# LTC3108breakoutSSOC.net
KiCad netlist of a schematic drawn in EAGLE
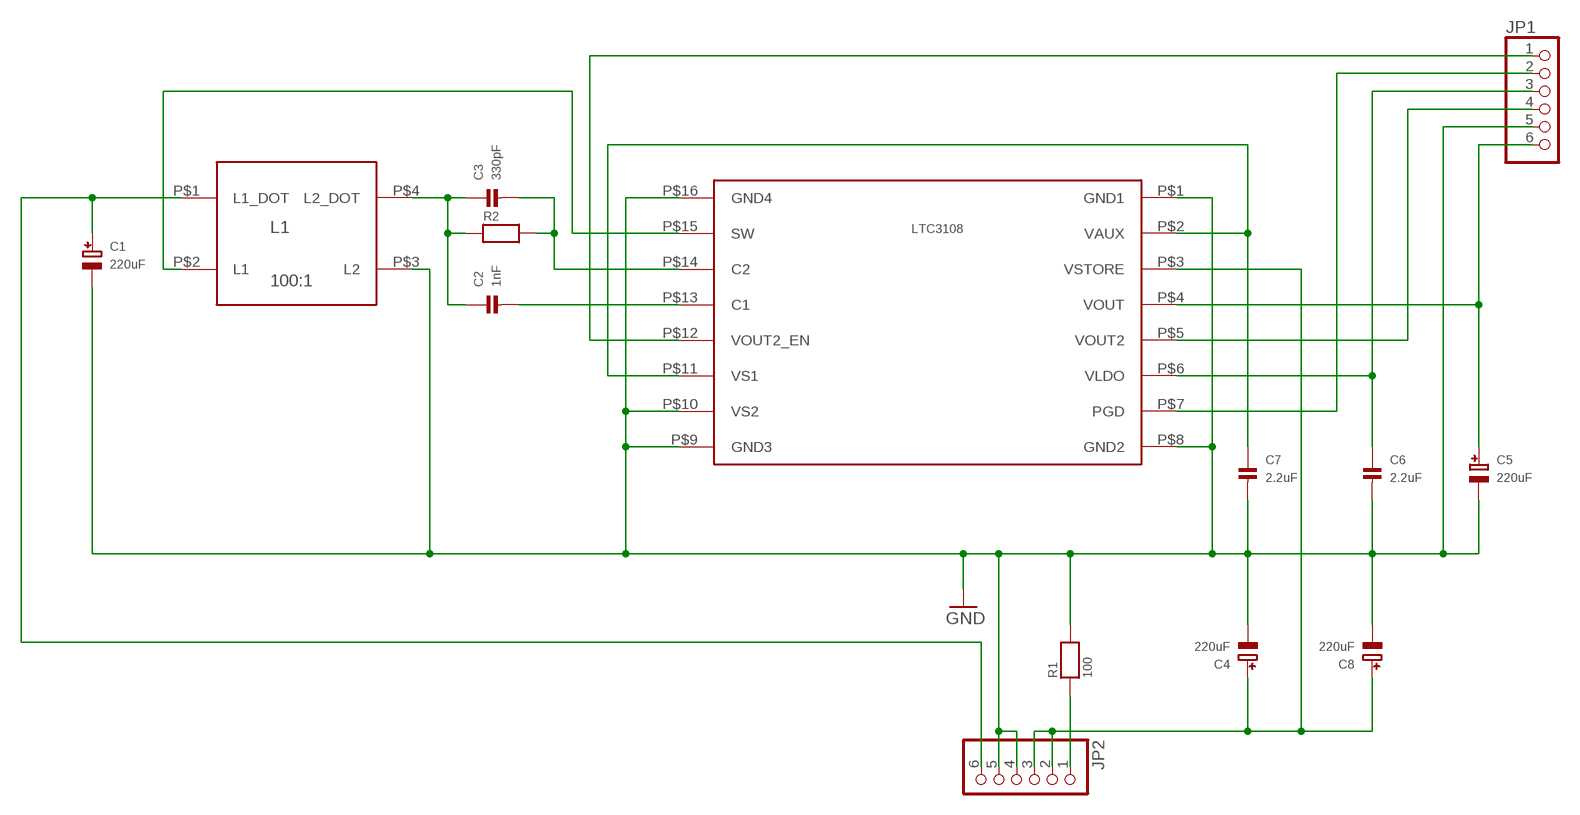
[diagram p0: schematic, sheet 1]

(export (version "E")
  (design (tool "Eeschema 10.0.6"))
  (components
    (comp (ref "C1")
      (value "220uF")
      (footprint "eagle-import:EIA7343-31_D-R")
      (libsource (lib "eagle-import") (part "CAP_TANTALUMD/7343_REFLOW"))
    )
    (comp (ref "C2")
      (value "1nF")
      (footprint "eagle-import:0603")
      (libsource (lib "eagle-import") (part "CAP_CERAMIC0603"))
    )
    (comp (ref "C3")
      (value "330pF")
      (footprint "eagle-import:0603")
      (libsource (lib "eagle-import") (part "CAP_CERAMIC0603"))
    )
    (comp (ref "C4")
      (value "220uF")
      (footprint "eagle-import:EIA7343-31_D-R")
      (libsource (lib "eagle-import") (part "CAP_TANTALUMD/7343_REFLOW"))
    )
    (comp (ref "C5")
      (value "220uF")
      (footprint "eagle-import:EIA7343-31_D-R")
      (libsource (lib "eagle-import") (part "CAP_TANTALUMD/7343_REFLOW"))
    )
    (comp (ref "C6")
      (value "2.2uF")
      (footprint "eagle-import:0603")
      (libsource (lib "eagle-import") (part "CAP_CERAMIC0603"))
    )
    (comp (ref "C7")
      (value "2.2uF")
      (footprint "eagle-import:0603")
      (libsource (lib "eagle-import") (part "CAP_CERAMIC0603"))
    )
    (comp (ref "C8")
      (value "220uF")
      (footprint "eagle-import:EIA7343-31_D-R")
      (libsource (lib "eagle-import") (part "CAP_TANTALUMD/7343_REFLOW"))
    )
    (comp (ref "JP1")
      (value "HEADER-1X6ROUND")
      (footprint "eagle-import:1X06_ROUND")
      (libsource (lib "eagle-import") (part "HEADER-1X6ROUND"))
    )
    (comp (ref "JP2")
      (value "HEADER-1X6ROUND")
      (footprint "eagle-import:1X06_ROUND")
      (libsource (lib "eagle-import") (part "HEADER-1X6ROUND"))
    )
    (comp (ref "L1")
      (value "100:1")
      (footprint "eagle-import:COILCRAFT_LPR6235")
      (libsource (lib "eagle-import") (part "COILCRAFT_LPR6235-752SML"))
    )
    (comp (ref "LTC3108")
      (value "LTC3108-SSOP")
      (footprint "eagle-import:SSOP-GN-16")
      (libsource (lib "eagle-import") (part "LTC3108-SSOP"))
    )
    (comp (ref "R1")
      (value "100")
      (footprint "eagle-import:0603")
      (libsource (lib "eagle-import") (part "RESISTOR0603"))
    )
    (comp (ref "R2")
      (value "RESISTOR0603")
      (footprint "eagle-import:0603")
      (libsource (lib "eagle-import") (part "RESISTOR0603"))
    )
  )
  (nets
    (net (code "1") (name "GND") (class "Default")
      (node (ref "C1") (pin "-") (pinfunction "-_-") (pintype "passive"))
      (node (ref "C4") (pin "-") (pinfunction "-_-") (pintype "passive"))
      (node (ref "C5") (pin "-") (pinfunction "-_-") (pintype "passive"))
      (node (ref "C6") (pin "2") (pinfunction "P$2_2") (pintype "passive"))
      (node (ref "C7") (pin "2") (pinfunction "P$2_2") (pintype "passive"))
      (node (ref "C8") (pin "-") (pinfunction "-_-") (pintype "passive"))
      (node (ref "JP1") (pin "5") (pinfunction "5_5") (pintype "passive"))
      (node (ref "JP2") (pin "4") (pinfunction "4_4") (pintype "passive"))
      (node (ref "JP2") (pin "5") (pinfunction "5_5") (pintype "passive"))
      (node (ref "L1") (pin "P$3") (pinfunction "L2_P$3") (pintype "bidirectional"))
      (node (ref "LTC3108") (pin "P$1") (pinfunction "GND1_P$1") (pintype "bidirectional"))
      (node (ref "LTC3108") (pin "P$10") (pinfunction "VS2_P$10") (pintype "bidirectional"))
      (node (ref "LTC3108") (pin "P$16") (pinfunction "GND4_P$16") (pintype "bidirectional"))
      (node (ref "LTC3108") (pin "P$8") (pinfunction "GND2_P$8") (pintype "bidirectional"))
      (node (ref "LTC3108") (pin "P$9") (pinfunction "GND3_P$9") (pintype "bidirectional"))
      (node (ref "R1") (pin "2") (pinfunction "2_2") (pintype "passive"))
    )
    (net (code "2") (name "Net-(C2-P$1)") (class "Default")
      (node (ref "C2") (pin "1") (pinfunction "P$1_1") (pintype "passive"))
      (node (ref "C3") (pin "1") (pinfunction "P$1_1") (pintype "passive"))
      (node (ref "L1") (pin "P$4") (pinfunction "L2_DOT_P$4") (pintype "bidirectional"))
      (node (ref "R2") (pin "1") (pinfunction "1_1") (pintype "passive"))
    )
    (net (code "3") (name "Net-(C2-P$2)") (class "Default")
      (node (ref "C2") (pin "2") (pinfunction "P$2_2") (pintype "passive"))
      (node (ref "LTC3108") (pin "P$13") (pinfunction "C1_P$13") (pintype "bidirectional"))
    )
    (net (code "4") (name "Net-(C3-P$2)") (class "Default")
      (node (ref "C3") (pin "2") (pinfunction "P$2_2") (pintype "passive"))
      (node (ref "LTC3108") (pin "P$14") (pinfunction "C2_P$14") (pintype "bidirectional"))
      (node (ref "R2") (pin "2") (pinfunction "2_2") (pintype "passive"))
    )
    (net (code "5") (name "Net-(C6-P$1)") (class "Default")
      (node (ref "C6") (pin "1") (pinfunction "P$1_1") (pintype "passive"))
      (node (ref "JP1") (pin "3") (pinfunction "3_3") (pintype "passive"))
      (node (ref "LTC3108") (pin "P$6") (pinfunction "VLDO_P$6") (pintype "bidirectional"))
    )
    (net (code "6") (name "Net-(C7-P$1)") (class "Default")
      (node (ref "C7") (pin "1") (pinfunction "P$1_1") (pintype "passive"))
      (node (ref "LTC3108") (pin "P$11") (pinfunction "VS1_P$11") (pintype "bidirectional"))
      (node (ref "LTC3108") (pin "P$2") (pinfunction "VAUX_P$2") (pintype "bidirectional"))
    )
    (net (code "7") (name "Net-(JP2-Pad1)") (class "Default")
      (node (ref "JP2") (pin "1") (pinfunction "1_1") (pintype "passive"))
      (node (ref "R1") (pin "1") (pinfunction "1_1") (pintype "passive"))
    )
    (net (code "8") (name "Net-(L1-L1)") (class "Default")
      (node (ref "L1") (pin "P$2") (pinfunction "L1_P$2") (pintype "bidirectional"))
      (node (ref "LTC3108") (pin "P$15") (pinfunction "SW_P$15") (pintype "bidirectional"))
    )
    (net (code "9") (name "Net-(L1-L1_DOT)") (class "Default")
      (node (ref "C1") (pin "+") (pinfunction "+_+") (pintype "passive"))
      (node (ref "JP2") (pin "6") (pinfunction "6_6") (pintype "passive"))
      (node (ref "L1") (pin "P$1") (pinfunction "L1_DOT_P$1") (pintype "bidirectional"))
    )
    (net (code "10") (name "Net-(LTC3108-PGD)") (class "Default")
      (node (ref "JP1") (pin "2") (pinfunction "2_2") (pintype "passive"))
      (node (ref "LTC3108") (pin "P$7") (pinfunction "PGD_P$7") (pintype "bidirectional"))
    )
    (net (code "11") (name "Net-(LTC3108-VOUT)") (class "Default")
      (node (ref "C5") (pin "+") (pinfunction "+_+") (pintype "passive"))
      (node (ref "JP1") (pin "6") (pinfunction "6_6") (pintype "passive"))
      (node (ref "LTC3108") (pin "P$4") (pinfunction "VOUT_P$4") (pintype "bidirectional"))
    )
    (net (code "12") (name "Net-(LTC3108-VOUT2)") (class "Default")
      (node (ref "JP1") (pin "4") (pinfunction "4_4") (pintype "passive"))
      (node (ref "LTC3108") (pin "P$5") (pinfunction "VOUT2_P$5") (pintype "bidirectional"))
    )
    (net (code "13") (name "Net-(LTC3108-VOUT2_EN)") (class "Default")
      (node (ref "JP1") (pin "1") (pinfunction "1_1") (pintype "passive"))
      (node (ref "LTC3108") (pin "P$12") (pinfunction "VOUT2_EN_P$12") (pintype "bidirectional"))
    )
    (net (code "14") (name "Net-(LTC3108-VSTORE)") (class "Default")
      (node (ref "C4") (pin "+") (pinfunction "+_+") (pintype "passive"))
      (node (ref "C8") (pin "+") (pinfunction "+_+") (pintype "passive"))
      (node (ref "JP2") (pin "2") (pinfunction "2_2") (pintype "passive"))
      (node (ref "JP2") (pin "3") (pinfunction "3_3") (pintype "passive"))
      (node (ref "LTC3108") (pin "P$3") (pinfunction "VSTORE_P$3") (pintype "bidirectional"))
    )
  )
)
